# amg8833.net
KiCad netlist of a schematic drawn in Altium Designer
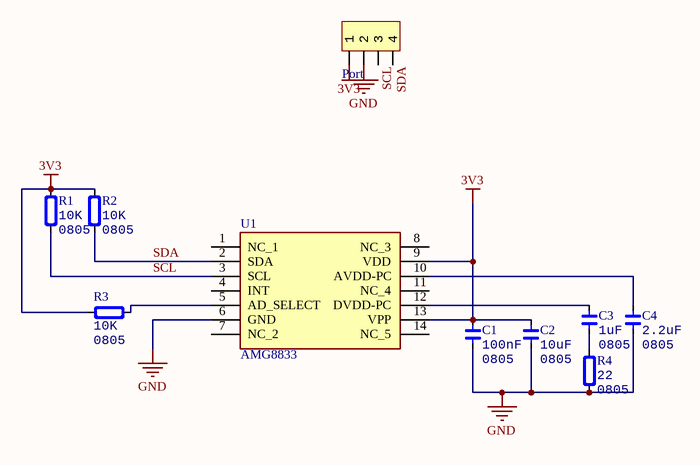
[diagram p0: amg8833.SchDoc]

(export (version "E")
  (design (tool "Eeschema 10.0.6"))
  (components
    (comp (ref "C1")
      (value "100nF")
      (footprint "CAP_0805")
      (description "Capacitor")
      (fields (field (name "TYPE") "0805") (field (name "Comment") "C0805"))
      (libsource (lib "Integrated_Library") (part "Cap_0805"))
    )
    (comp (ref "C2")
      (value "10uF")
      (footprint "CAP_0805")
      (description "Capacitor")
      (fields (field (name "TYPE") "0805") (field (name "Comment") "C0805"))
      (libsource (lib "Integrated_Library") (part "Cap_0805"))
    )
    (comp (ref "C3")
      (value "1uF")
      (footprint "CAP_0805")
      (description "Capacitor")
      (fields (field (name "TYPE") "0805") (field (name "Comment") "C0805"))
      (libsource (lib "Integrated_Library") (part "Cap_0805"))
    )
    (comp (ref "C4")
      (value "2.2uF")
      (footprint "CAP_0805")
      (description "Capacitor")
      (fields (field (name "TYPE") "0805") (field (name "Comment") "C0805"))
      (libsource (lib "Integrated_Library") (part "Cap_0805"))
    )
    (comp (ref "Port")
      (value "HDR1x4_2.54")
      (footprint "HDR1x4_2.54_180")
      (description "Header")
      (libsource (lib "Integrated_Library") (part "HDR1x4_2.54"))
    )
    (comp (ref "R1")
      (value "10K")
      (footprint "RES_0805")
      (description "Resistor")
      (fields (field (name "TYPE") "0805") (field (name "Comment") "R0805"))
      (libsource (lib "Integrated_Library") (part "Res_0805"))
    )
    (comp (ref "R2")
      (value "10K")
      (footprint "RES_0805")
      (description "Resistor")
      (fields (field (name "TYPE") "0805") (field (name "Comment") "R0805"))
      (libsource (lib "Integrated_Library") (part "Res_0805"))
    )
    (comp (ref "R3")
      (value "10K")
      (footprint "RES_0805")
      (description "Resistor")
      (fields (field (name "TYPE") "0805") (field (name "Comment") "R0805"))
      (libsource (lib "Integrated_Library") (part "Res_0805"))
    )
    (comp (ref "R4")
      (value "22")
      (footprint "RES_0805")
      (description "Resistor")
      (fields (field (name "TYPE") "0805") (field (name "Comment") "R0805"))
      (libsource (lib "Integrated_Library") (part "Res_0805"))
    )
    (comp (ref "U1") (value "AMG8833") (footprint "AMG8833") (libsource (lib "PPD") (part "AMG8833")))
  )
  (nets
    (net (code "1") (name "/SCL") (class "Default")
      (node (ref "Port") (pin "3") (pinfunction "3_3") (pintype "passive"))
      (node (ref "R1") (pin "1") (pinfunction "1_1") (pintype "passive"))
      (node (ref "U1") (pin "3") (pinfunction "SCL_3") (pintype "passive"))
    )
    (net (code "2") (name "/SDA") (class "Default")
      (node (ref "Port") (pin "4") (pinfunction "4_4") (pintype "passive"))
      (node (ref "R2") (pin "1") (pinfunction "1_1") (pintype "passive"))
      (node (ref "U1") (pin "2") (pinfunction "SDA_2") (pintype "passive"))
    )
    (net (code "3") (name "3V3") (class "Default")
      (node (ref "C1") (pin "2") (pinfunction "2_2") (pintype "passive"))
      (node (ref "C2") (pin "2") (pinfunction "2_2") (pintype "passive"))
      (node (ref "Port") (pin "1") (pinfunction "1_1") (pintype "passive"))
      (node (ref "R1") (pin "2") (pinfunction "2_2") (pintype "passive"))
      (node (ref "R2") (pin "2") (pinfunction "2_2") (pintype "passive"))
      (node (ref "R3") (pin "2") (pinfunction "2_2") (pintype "passive"))
      (node (ref "U1") (pin "13") (pinfunction "VPP_13") (pintype "passive"))
      (node (ref "U1") (pin "9") (pinfunction "VDD_9") (pintype "passive"))
    )
    (net (code "4") (name "GND") (class "Default")
      (node (ref "C1") (pin "1") (pinfunction "1_1") (pintype "passive"))
      (node (ref "C2") (pin "1") (pinfunction "1_1") (pintype "passive"))
      (node (ref "C4") (pin "1") (pinfunction "1_1") (pintype "passive"))
      (node (ref "Port") (pin "2") (pinfunction "2_2") (pintype "passive"))
      (node (ref "R4") (pin "1") (pinfunction "1_1") (pintype "passive"))
      (node (ref "U1") (pin "6") (pinfunction "GND_6") (pintype "passive"))
    )
    (net (code "5") (name "Net-(C3-Pad1)") (class "Default")
      (node (ref "C3") (pin "1") (pinfunction "1_1") (pintype "passive"))
      (node (ref "R4") (pin "2") (pinfunction "2_2") (pintype "passive"))
    )
    (net (code "6") (name "Net-(U1-AD_SELECT)") (class "Default")
      (node (ref "R3") (pin "1") (pinfunction "1_1") (pintype "passive"))
      (node (ref "U1") (pin "5") (pinfunction "AD_SELECT_5") (pintype "passive"))
    )
    (net (code "7") (name "Net-(U1-AVDD-PC)") (class "Default")
      (node (ref "C4") (pin "2") (pinfunction "2_2") (pintype "passive"))
      (node (ref "U1") (pin "10") (pinfunction "AVDD-PC_10") (pintype "passive"))
    )
    (net (code "8") (name "Net-(U1-DVDD-PC)") (class "Default")
      (node (ref "C3") (pin "2") (pinfunction "2_2") (pintype "passive"))
      (node (ref "U1") (pin "12") (pinfunction "DVDD-PC_12") (pintype "passive"))
    )
    (net (code "9") (name "unconnected-(U1-INT-Pad4)") (class "Default")
      (node (ref "U1") (pin "4") (pinfunction "INT_4") (pintype "passive"))
    )
    (net (code "10") (name "unconnected-(U1-NC_1-Pad1)") (class "Default")
      (node (ref "U1") (pin "1") (pinfunction "NC_1_1") (pintype "passive"))
    )
    (net (code "11") (name "unconnected-(U1-NC_2-Pad7)") (class "Default")
      (node (ref "U1") (pin "7") (pinfunction "NC_2_7") (pintype "passive"))
    )
    (net (code "12") (name "unconnected-(U1-NC_3-Pad8)") (class "Default")
      (node (ref "U1") (pin "8") (pinfunction "NC_3_8") (pintype "passive"))
    )
    (net (code "13") (name "unconnected-(U1-NC_4-Pad11)") (class "Default")
      (node (ref "U1") (pin "11") (pinfunction "NC_4_11") (pintype "passive"))
    )
    (net (code "14") (name "unconnected-(U1-NC_5-Pad14)") (class "Default")
      (node (ref "U1") (pin "14") (pinfunction "NC_5_14") (pintype "passive"))
    )
  )
)
